# Motor_Schematic.net
KiCad netlist of a schematic drawn in Altium Designer
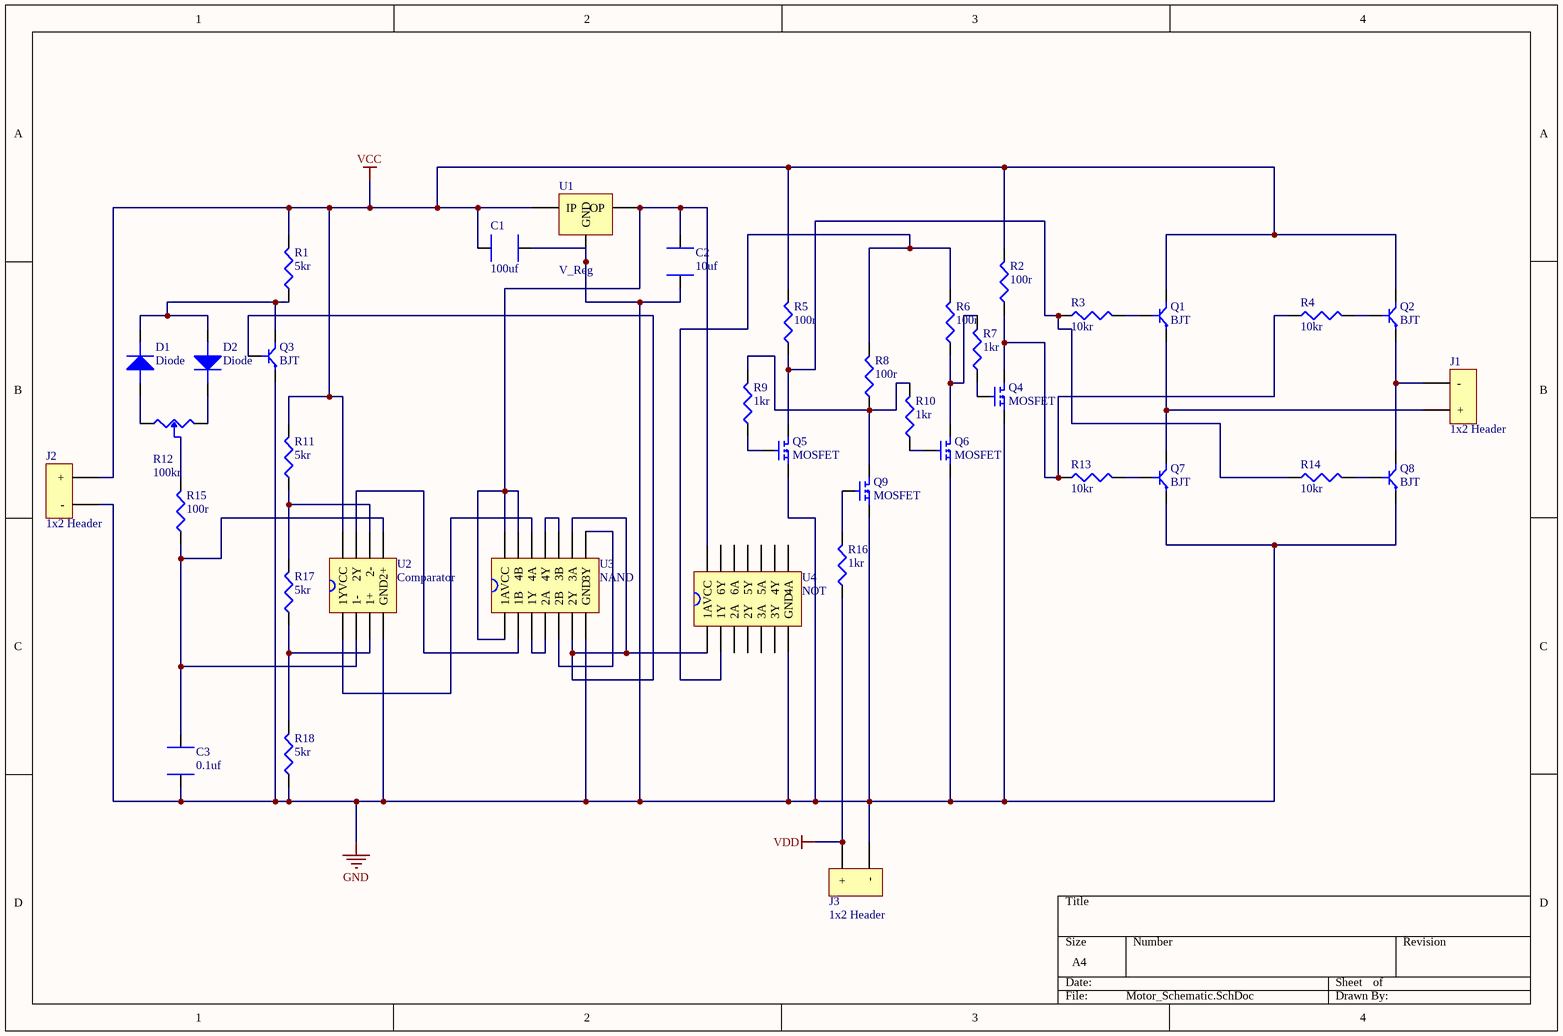
[diagram p0: Motor_Schematic.SchDoc]

(export (version "E")
  (design (tool "Eeschema 10.0.6"))
  (components
    (comp (ref "C1")
      (value "100uf")
      (footprint "100UF")
      (description "CAP CER 100UF 10V Y5V RADIAL")
      (fields (field (name "MANUFACTURER") "TDK") (field (name "MANUFACTURER PART NUMBER") "FK22Y5V1A107Z"))
      (libsource (lib "Sch_Lib") (part "FK22Y5V1A107Z"))
    )
    (comp (ref "C2")
      (value "10uf")
      (footprint "10UF")
      (description "Cap Ceramic 10uF 25V X7R 20% Radial 5mm 125°C Bulk")
      (fields
        (field (name "MANUFACTURER") "TDK")
        (field (name "MANUFACTURER PART NUMBER") "FK20X7R1E106MR000")
      )
      (libsource (lib "Sch_Lib") (part "FK20X7R1E106MR000"))
    )
    (comp (ref "C3")
      (value "0.1uf")
      (footprint "0.1UF")
      (description "Cap Ceramic 0.1uF 50V X7R 10% Radial 5.08mm (0.01%FR) 125°C Bulk")
      (fields
        (field (name "MANUFACTURER") "KEMET")
        (field (name "MANUFACTURER PART NUMBER") "M39014/01-1553")
      )
      (libsource (lib "Sch_Lib") (part "M39014/01-1553"))
    )
    (comp (ref "D1")
      (value "Diode")
      (footprint "Diode")
      (description "DIODE GEN PURP 50V 1A DO41")
      (fields (field (name "MANUFACTURER") "Diodes") (field (name "MANUFACTURER PART NUMBER") "1N4001G-T"))
      (libsource (lib "Sch_Lib") (part "1N4001G-T"))
    )
    (comp (ref "D2")
      (value "Diode")
      (footprint "Diode")
      (description "DIODE GEN PURP 50V 1A DO41")
      (fields (field (name "MANUFACTURER") "Diodes") (field (name "MANUFACTURER PART NUMBER") "1N4001G-T"))
      (libsource (lib "Sch_Lib") (part "1N4001G-T"))
    )
    (comp (ref "J1")
      (value "1x2 Header")
      (footprint "HDR1X2")
      (description "Conn Wire to Board HDR 2 POS 2.54mm Solder ST Thru-Hole Bag")
      (fields (field (name "MANUFACTURER") "Molex") (field (name "MANUFACTURER PART NUMBER") "22-29-2021"))
      (libsource (lib "") (part "22-29-2021_2"))
    )
    (comp (ref "J2")
      (value "1x2 Header")
      (footprint "HDR1X2")
      (description "Conn Wire to Board HDR 2 POS 2.54mm Solder ST Thru-Hole Bag")
      (fields (field (name "MANUFACTURER") "Molex") (field (name "MANUFACTURER PART NUMBER") "22-29-2021"))
      (libsource (lib "Sch_Lib") (part "22-29-2021"))
    )
    (comp (ref "J3")
      (value "1x2 Header")
      (footprint "HDR1X2")
      (description "Conn Wire to Board HDR 2 POS 2.54mm Solder ST Thru-Hole Bag")
      (fields (field (name "MANUFACTURER") "Molex") (field (name "MANUFACTURER PART NUMBER") "22-29-2021"))
      (libsource (lib "") (part "22-29-2021_1"))
    )
    (comp (ref "Q1")
      (value "BJT")
      (footprint "BJT")
      (description "TRANS NPN 40V 0.8A TO-18")
      (fields
        (field (name "MANUFACTURER") "Central Semiconductor")
        (field (name "MANUFACTURER PART NUMBER") "2N2222A")
      )
      (libsource (lib "Sch_Lib") (part "2N2222A"))
    )
    (comp (ref "Q2")
      (value "BJT")
      (footprint "BJT")
      (description "TRANS NPN 40V 0.8A TO-18")
      (fields
        (field (name "MANUFACTURER") "Central Semiconductor")
        (field (name "MANUFACTURER PART NUMBER") "2N2222A")
      )
      (libsource (lib "Sch_Lib") (part "2N2222A"))
    )
    (comp (ref "Q3")
      (value "BJT")
      (footprint "BJT")
      (description "TRANS NPN 40V 0.8A TO-18")
      (fields
        (field (name "MANUFACTURER") "Central Semiconductor")
        (field (name "MANUFACTURER PART NUMBER") "2N2222A")
      )
      (libsource (lib "Sch_Lib") (part "2N2222A"))
    )
    (comp (ref "Q4")
      (value "MOSFET")
      (footprint "MOSFET")
      (description "Trans MOSFET N-CH 60V 0.2A 3-Pin TO-92 Ammo")
      (fields
        (field (name "MANUFACTURER") "ON Semiconductor / Fairchild")
        (field (name "MANUFACTURER PART NUMBER") "2N7000TA")
      )
      (libsource (lib "Sch_Lib") (part "2N7000TA"))
    )
    (comp (ref "Q5")
      (value "MOSFET")
      (footprint "MOSFET")
      (description "Trans MOSFET N-CH 60V 0.2A 3-Pin TO-92 Ammo")
      (fields
        (field (name "MANUFACTURER") "ON Semiconductor / Fairchild")
        (field (name "MANUFACTURER PART NUMBER") "2N7000TA")
      )
      (libsource (lib "Sch_Lib") (part "2N7000TA"))
    )
    (comp (ref "Q6")
      (value "MOSFET")
      (footprint "MOSFET")
      (description "Trans MOSFET N-CH 60V 0.2A 3-Pin TO-92 Ammo")
      (fields
        (field (name "MANUFACTURER") "ON Semiconductor / Fairchild")
        (field (name "MANUFACTURER PART NUMBER") "2N7000TA")
      )
      (libsource (lib "Sch_Lib") (part "2N7000TA"))
    )
    (comp (ref "Q7")
      (value "BJT")
      (footprint "BJT")
      (description "TRANS NPN 40V 0.8A TO-18")
      (fields
        (field (name "MANUFACTURER") "Central Semiconductor")
        (field (name "MANUFACTURER PART NUMBER") "2N2222A")
      )
      (libsource (lib "Sch_Lib") (part "2N2222A"))
    )
    (comp (ref "Q8")
      (value "BJT")
      (footprint "BJT")
      (description "TRANS NPN 40V 0.8A TO-18")
      (fields
        (field (name "MANUFACTURER") "Central Semiconductor")
        (field (name "MANUFACTURER PART NUMBER") "2N2222A")
      )
      (libsource (lib "Sch_Lib") (part "2N2222A"))
    )
    (comp (ref "Q9")
      (value "MOSFET")
      (footprint "MOSFET")
      (description "Trans MOSFET N-CH 60V 0.2A 3-Pin TO-92 Ammo")
      (fields
        (field (name "MANUFACTURER") "ON Semiconductor / Fairchild")
        (field (name "MANUFACTURER PART NUMBER") "2N7000TA")
      )
      (libsource (lib "Sch_Lib") (part "2N7000TA"))
    )
    (comp (ref "R1")
      (value "5kr")
      (footprint "5KR")
      (description "Metal Film Resistors - Through Hole 1/8watt 5Kohms 1% 100ppm Non Std")
      (fields
        (field (name "MANUFACTURER") "Vishay Dale")
        (field (name "MANUFACTURER PART NUMBER") "RN55D5001FB14")
      )
      (libsource (lib "Sch_Lib") (part "RN55D5001FB14"))
    )
    (comp (ref "R2")
      (value "100r")
      (footprint "100R")
      (description "RESISTOR METAL FILM 1W 100 OHM")
      (fields
        (field (name "MANUFACTURER") "Vishay Dale")
        (field (name "MANUFACTURER PART NUMBER") "CPF1100R00JKEE6")
      )
      (libsource (lib "Sch_Lib") (part "CPF1100R00JKEE6"))
    )
    (comp (ref "R3")
      (value "10kr")
      (footprint "10kr")
      (description "RESISTOR METAL FILM 1W 10.0K OHM")
      (fields
        (field (name "MANUFACTURER") "Vishay Dale")
        (field (name "MANUFACTURER PART NUMBER") "CPF110K000FKEE6")
      )
      (libsource (lib "Sch_Lib") (part "CPF110K000FKEE6"))
    )
    (comp (ref "R4")
      (value "10kr")
      (footprint "10kr")
      (description "RESISTOR METAL FILM 1W 10.0K OHM")
      (fields
        (field (name "MANUFACTURER") "Vishay Dale")
        (field (name "MANUFACTURER PART NUMBER") "CPF110K000FKEE6")
      )
      (libsource (lib "Sch_Lib") (part "CPF110K000FKEE6"))
    )
    (comp (ref "R5")
      (value "100r")
      (footprint "100R")
      (description "RESISTOR METAL FILM 1W 100 OHM")
      (fields
        (field (name "MANUFACTURER") "Vishay Dale")
        (field (name "MANUFACTURER PART NUMBER") "CPF1100R00JKEE6")
      )
      (libsource (lib "Sch_Lib") (part "CPF1100R00JKEE6"))
    )
    (comp (ref "R6")
      (value "100r")
      (footprint "100R")
      (description "RESISTOR METAL FILM 1W 100 OHM")
      (fields
        (field (name "MANUFACTURER") "Vishay Dale")
        (field (name "MANUFACTURER PART NUMBER") "CPF1100R00JKEE6")
      )
      (libsource (lib "Sch_Lib") (part "CPF1100R00JKEE6"))
    )
    (comp (ref "R7")
      (value "1kr")
      (footprint "1KR")
      (description "RESISTOR 1.0K OHM 1/4W .01% WW")
      (fields
        (field (name "MANUFACTURER") "Vishay Dale")
        (field (name "MANUFACTURER PART NUMBER") "MR1061K0000TAE66")
      )
      (libsource (lib "Sch_Lib") (part "MR1061K0000TAE66"))
    )
    (comp (ref "R8")
      (value "100r")
      (footprint "100R")
      (description "RESISTOR METAL FILM 1W 100 OHM")
      (fields
        (field (name "MANUFACTURER") "Vishay Dale")
        (field (name "MANUFACTURER PART NUMBER") "CPF1100R00JKEE6")
      )
      (libsource (lib "Sch_Lib") (part "CPF1100R00JKEE6"))
    )
    (comp (ref "R9")
      (value "1kr")
      (footprint "1KR")
      (description "RESISTOR 1.0K OHM 1/4W .01% WW")
      (fields
        (field (name "MANUFACTURER") "Vishay Dale")
        (field (name "MANUFACTURER PART NUMBER") "MR1061K0000TAE66")
      )
      (libsource (lib "Sch_Lib") (part "MR1061K0000TAE66"))
    )
    (comp (ref "R10")
      (value "1kr")
      (footprint "1KR")
      (description "RESISTOR 1.0K OHM 1/4W .01% WW")
      (fields
        (field (name "MANUFACTURER") "Vishay Dale")
        (field (name "MANUFACTURER PART NUMBER") "MR1061K0000TAE66")
      )
      (libsource (lib "Sch_Lib") (part "MR1061K0000TAE66"))
    )
    (comp (ref "R11")
      (value "5kr")
      (footprint "5KR")
      (description "Metal Film Resistors - Through Hole 1/8watt 5Kohms 1% 100ppm Non Std")
      (fields
        (field (name "MANUFACTURER") "Vishay Dale")
        (field (name "MANUFACTURER PART NUMBER") "RN55D5001FB14")
      )
      (libsource (lib "Sch_Lib") (part "RN55D5001FB14"))
    )
    (comp (ref "R12")
      (value "100kr")
      (footprint "POT")
      (description "TRIMMER 100K OHM 0.75W PC PIN")
      (fields (field (name "MANUFACTURER") "TT BI") (field (name "MANUFACTURER PART NUMBER") "89PR100KLF"))
      (libsource (lib "Sch_Lib") (part "89PR100KLF"))
    )
    (comp (ref "R13")
      (value "10kr")
      (footprint "10kr")
      (description "RESISTOR METAL FILM 1W 10.0K OHM")
      (fields
        (field (name "MANUFACTURER") "Vishay Dale")
        (field (name "MANUFACTURER PART NUMBER") "CPF110K000FKEE6")
      )
      (libsource (lib "Sch_Lib") (part "CPF110K000FKEE6"))
    )
    (comp (ref "R14")
      (value "10kr")
      (footprint "10kr")
      (description "RESISTOR METAL FILM 1W 10.0K OHM")
      (fields
        (field (name "MANUFACTURER") "Vishay Dale")
        (field (name "MANUFACTURER PART NUMBER") "CPF110K000FKEE6")
      )
      (libsource (lib "Sch_Lib") (part "CPF110K000FKEE6"))
    )
    (comp (ref "R15")
      (value "100r")
      (footprint "100R")
      (description "RESISTOR METAL FILM 1W 100 OHM")
      (fields
        (field (name "MANUFACTURER") "Vishay Dale")
        (field (name "MANUFACTURER PART NUMBER") "CPF1100R00JKEE6")
      )
      (libsource (lib "Sch_Lib") (part "CPF1100R00JKEE6"))
    )
    (comp (ref "R16")
      (value "1kr")
      (footprint "1KR")
      (description "RESISTOR 1.0K OHM 1/4W .01% WW")
      (fields
        (field (name "MANUFACTURER") "Vishay Dale")
        (field (name "MANUFACTURER PART NUMBER") "MR1061K0000TAE66")
      )
      (libsource (lib "Sch_Lib") (part "MR1061K0000TAE66"))
    )
    (comp (ref "R17")
      (value "5kr")
      (footprint "5KR")
      (description "Metal Film Resistors - Through Hole 1/8watt 5Kohms 1% 100ppm Non Std")
      (fields
        (field (name "MANUFACTURER") "Vishay Dale")
        (field (name "MANUFACTURER PART NUMBER") "RN55D5001FB14")
      )
      (libsource (lib "Sch_Lib") (part "RN55D5001FB14"))
    )
    (comp (ref "R18")
      (value "5kr")
      (footprint "5KR")
      (description "Metal Film Resistors - Through Hole 1/8watt 5Kohms 1% 100ppm Non Std")
      (fields
        (field (name "MANUFACTURER") "Vishay Dale")
        (field (name "MANUFACTURER PART NUMBER") "RN55D5001FB14")
      )
      (libsource (lib "Sch_Lib") (part "RN55D5001FB14"))
    )
    (comp (ref "U1")
      (value "V_Reg")
      (footprint "V_REG")
      (description "IC REG LINEAR 5V 1A TO220-3")
      (fields
        (field (name "MANUFACTURER") "TI National Semiconductor")
        (field (name "MANUFACTURER PART NUMBER") "LM340T-5.0")
      )
      (libsource (lib "Sch_Lib") (part "LM340T-5.0"))
    )
    (comp (ref "U2")
      (value "Comparator")
      (footprint "COMP")
      (description "Comparator Dual ±18V/36V 8-Pin Micro T/R")
      (fields
        (field (name "MANUFACTURER") "ON Semiconductor")
        (field (name "MANUFACTURER PART NUMBER") "LM2903DMR2G")
      )
      (libsource (lib "Sch_Lib") (part "LM2903DMR2G"))
    )
    (comp (ref "U3")
      (value "NAND")
      (footprint "NAND")
      (description "NAND Gate 4-Element 2-IN Bipolar 14-Pin PDIP Tube")
      (fields
        (field (name "MANUFACTURER") "Texas Instruments")
        (field (name "MANUFACTURER PART NUMBER") "SN74AS1000AN")
      )
      (libsource (lib "Sch_Lib") (part "SN74AS1000AN"))
    )
    (comp (ref "U4")
      (value "NOT")
      (footprint "NOT")
      (description "Inverter Schmitt Trigger 6-Element CMOS 14-Pin SOP T/R")
      (fields
        (field (name "MANUFACTURER") "Toshiba")
        (field (name "MANUFACTURER PART NUMBER") "TC74AC14F(EL,F)")
      )
      (libsource (lib "Sch_Lib") (part "TC74AC14F(EL,F)"))
    )
  )
  (nets
    (net (code "1") (name "GND") (class "Default")
      (node (ref "C1") (pin "2") (pinfunction "2_2") (pintype "passive"))
      (node (ref "C2") (pin "1") (pinfunction "1_1") (pintype "passive"))
      (node (ref "C3") (pin "1") (pinfunction "1_1") (pintype "passive"))
      (node (ref "J2") (pin "2") (pinfunction "-_2") (pintype "passive"))
      (node (ref "J3") (pin "2") (pinfunction "-_2") (pintype "passive"))
      (node (ref "Q3") (pin "3") (pinfunction "3_3") (pintype "passive"))
      (node (ref "Q4") (pin "3") (pinfunction "3_3") (pintype "passive"))
      (node (ref "Q5") (pin "3") (pinfunction "3_3") (pintype "passive"))
      (node (ref "Q6") (pin "3") (pinfunction "3_3") (pintype "passive"))
      (node (ref "Q7") (pin "3") (pinfunction "3_3") (pintype "passive"))
      (node (ref "Q8") (pin "3") (pinfunction "3_3") (pintype "passive"))
      (node (ref "Q9") (pin "3") (pinfunction "3_3") (pintype "passive"))
      (node (ref "R18") (pin "1") (pinfunction "1_1") (pintype "passive"))
      (node (ref "U1") (pin "2") (pinfunction "GND_2") (pintype "passive"))
      (node (ref "U2") (pin "4") (pinfunction "GND_4") (pintype "passive"))
      (node (ref "U3") (pin "7") (pinfunction "GND_7") (pintype "passive"))
      (node (ref "U4") (pin "7") (pinfunction "GND_7") (pintype "passive"))
    )
    (net (code "2") (name "Net-(D1-Pad1)") (class "Default")
      (node (ref "D1") (pin "1") (pinfunction "1_1") (pintype "passive"))
      (node (ref "D2") (pin "2") (pinfunction "2_2") (pintype "passive"))
      (node (ref "Q3") (pin "1") (pinfunction "1_1") (pintype "passive"))
      (node (ref "R1") (pin "1") (pinfunction "1_1") (pintype "passive"))
    )
    (net (code "3") (name "Net-(D1-Pad2)") (class "Default")
      (node (ref "D1") (pin "2") (pinfunction "2_2") (pintype "passive"))
      (node (ref "R12") (pin "3") (pinfunction "3_3") (pintype "passive"))
    )
    (net (code "4") (name "Net-(D2-Pad1)") (class "Default")
      (node (ref "D2") (pin "1") (pinfunction "1_1") (pintype "passive"))
      (node (ref "R12") (pin "1") (pinfunction "1_1") (pintype "passive"))
    )
    (net (code "5") (name "Net-(J1-+)") (class "Default")
      (node (ref "J1") (pin "1") (pinfunction "+_1") (pintype "passive"))
      (node (ref "Q1") (pin "3") (pinfunction "3_3") (pintype "passive"))
      (node (ref "Q7") (pin "1") (pinfunction "1_1") (pintype "passive"))
    )
    (net (code "6") (name "Net-(J1--)") (class "Default")
      (node (ref "J1") (pin "2") (pinfunction "-_2") (pintype "passive"))
      (node (ref "Q2") (pin "3") (pinfunction "3_3") (pintype "passive"))
      (node (ref "Q8") (pin "1") (pinfunction "1_1") (pintype "passive"))
    )
    (net (code "7") (name "Net-(Q1-Pad2)") (class "Default")
      (node (ref "Q1") (pin "2") (pinfunction "2_2") (pintype "passive"))
      (node (ref "R3") (pin "2") (pinfunction "2_2") (pintype "passive"))
    )
    (net (code "8") (name "Net-(Q2-Pad2)") (class "Default")
      (node (ref "Q2") (pin "2") (pinfunction "2_2") (pintype "passive"))
      (node (ref "R4") (pin "2") (pinfunction "2_2") (pintype "passive"))
    )
    (net (code "9") (name "Net-(Q4-Pad1)") (class "Default")
      (node (ref "Q4") (pin "1") (pinfunction "1_1") (pintype "passive"))
      (node (ref "R13") (pin "1") (pinfunction "1_1") (pintype "passive"))
      (node (ref "R2") (pin "1") (pinfunction "1_1") (pintype "passive"))
      (node (ref "R4") (pin "1") (pinfunction "1_1") (pintype "passive"))
    )
    (net (code "10") (name "Net-(Q4-Pad2)") (class "Default")
      (node (ref "Q4") (pin "2") (pinfunction "2_2") (pintype "passive"))
      (node (ref "R7") (pin "1") (pinfunction "1_1") (pintype "passive"))
    )
    (net (code "11") (name "Net-(Q5-Pad1)") (class "Default")
      (node (ref "Q5") (pin "1") (pinfunction "1_1") (pintype "passive"))
      (node (ref "R14") (pin "1") (pinfunction "1_1") (pintype "passive"))
      (node (ref "R3") (pin "1") (pinfunction "1_1") (pintype "passive"))
      (node (ref "R5") (pin "1") (pinfunction "1_1") (pintype "passive"))
    )
    (net (code "12") (name "Net-(Q5-Pad2)") (class "Default")
      (node (ref "Q5") (pin "2") (pinfunction "2_2") (pintype "passive"))
      (node (ref "R9") (pin "1") (pinfunction "1_1") (pintype "passive"))
    )
    (net (code "13") (name "Net-(Q6-Pad1)") (class "Default")
      (node (ref "Q6") (pin "1") (pinfunction "1_1") (pintype "passive"))
      (node (ref "R6") (pin "1") (pinfunction "1_1") (pintype "passive"))
      (node (ref "R7") (pin "2") (pinfunction "2_2") (pintype "passive"))
    )
    (net (code "14") (name "Net-(Q6-Pad2)") (class "Default")
      (node (ref "Q6") (pin "2") (pinfunction "2_2") (pintype "passive"))
      (node (ref "R10") (pin "1") (pinfunction "1_1") (pintype "passive"))
    )
    (net (code "15") (name "Net-(Q7-Pad2)") (class "Default")
      (node (ref "Q7") (pin "2") (pinfunction "2_2") (pintype "passive"))
      (node (ref "R13") (pin "2") (pinfunction "2_2") (pintype "passive"))
    )
    (net (code "16") (name "Net-(Q8-Pad2)") (class "Default")
      (node (ref "Q8") (pin "2") (pinfunction "2_2") (pintype "passive"))
      (node (ref "R14") (pin "2") (pinfunction "2_2") (pintype "passive"))
    )
    (net (code "17") (name "Net-(Q9-Pad1)") (class "Default")
      (node (ref "Q9") (pin "1") (pinfunction "1_1") (pintype "passive"))
      (node (ref "R10") (pin "2") (pinfunction "2_2") (pintype "passive"))
      (node (ref "R8") (pin "1") (pinfunction "1_1") (pintype "passive"))
      (node (ref "R9") (pin "2") (pinfunction "2_2") (pintype "passive"))
    )
    (net (code "18") (name "Net-(Q9-Pad2)") (class "Default")
      (node (ref "Q9") (pin "2") (pinfunction "2_2") (pintype "passive"))
      (node (ref "R16") (pin "2") (pinfunction "2_2") (pintype "passive"))
    )
    (net (code "19") (name "Net-(R12-Pad2)") (class "Default")
      (node (ref "R12") (pin "2") (pinfunction "2_2") (pintype "passive"))
      (node (ref "R15") (pin "2") (pinfunction "2_2") (pintype "passive"))
    )
    (net (code "20") (name "Net-(U1-OP)") (class "Default")
      (node (ref "C2") (pin "2") (pinfunction "2_2") (pintype "passive"))
      (node (ref "U1") (pin "3") (pinfunction "OP_3") (pintype "passive"))
      (node (ref "U3") (pin "1") (pinfunction "1A_1") (pintype "passive"))
      (node (ref "U3") (pin "13") (pinfunction "4B_13") (pintype "passive"))
      (node (ref "U3") (pin "14") (pinfunction "VCC_14") (pintype "passive"))
      (node (ref "U4") (pin "14") (pinfunction "VCC_14") (pintype "passive"))
    )
    (net (code "21") (name "Net-(U2-1+)") (class "Default")
      (node (ref "R17") (pin "1") (pinfunction "1_1") (pintype "passive"))
      (node (ref "R18") (pin "2") (pinfunction "2_2") (pintype "passive"))
      (node (ref "U2") (pin "3") (pinfunction "1+_3") (pintype "passive"))
    )
    (net (code "22") (name "Net-(U2-1-)") (class "Default")
      (node (ref "C3") (pin "2") (pinfunction "2_2") (pintype "passive"))
      (node (ref "R15") (pin "1") (pinfunction "1_1") (pintype "passive"))
      (node (ref "U2") (pin "2") (pinfunction "1-_2") (pintype "passive"))
      (node (ref "U2") (pin "5") (pinfunction "2+_5") (pintype "passive"))
    )
    (net (code "23") (name "Net-(U2-1Y)") (class "Default")
      (node (ref "U2") (pin "1") (pinfunction "1Y_1") (pintype "passive"))
      (node (ref "U3") (pin "12") (pinfunction "4A_12") (pintype "passive"))
    )
    (net (code "24") (name "Net-(U2-2-)") (class "Default")
      (node (ref "R11") (pin "1") (pinfunction "1_1") (pintype "passive"))
      (node (ref "R17") (pin "2") (pinfunction "2_2") (pintype "passive"))
      (node (ref "U2") (pin "6") (pinfunction "2-_6") (pintype "passive"))
    )
    (net (code "25") (name "Net-(U2-2Y)") (class "Default")
      (node (ref "U2") (pin "7") (pinfunction "2Y_7") (pintype "passive"))
      (node (ref "U3") (pin "2") (pinfunction "1B_2") (pintype "passive"))
    )
    (net (code "26") (name "Net-(U3-1Y)") (class "Default")
      (node (ref "U3") (pin "3") (pinfunction "1Y_3") (pintype "passive"))
      (node (ref "U3") (pin "4") (pinfunction "2A_4") (pintype "passive"))
    )
    (net (code "27") (name "Net-(U3-2B)") (class "Default")
      (node (ref "U3") (pin "5") (pinfunction "2B_5") (pintype "passive"))
      (node (ref "U3") (pin "8") (pinfunction "3Y_8") (pintype "passive"))
    )
    (net (code "28") (name "Net-(U3-2Y)") (class "Default")
      (node (ref "Q3") (pin "2") (pinfunction "2_2") (pintype "passive"))
      (node (ref "U3") (pin "6") (pinfunction "2Y_6") (pintype "passive"))
      (node (ref "U3") (pin "9") (pinfunction "3A_9") (pintype "passive"))
      (node (ref "U4") (pin "1") (pinfunction "1A_1") (pintype "passive"))
    )
    (net (code "29") (name "Net-(U3-3B)") (class "Default")
      (node (ref "U3") (pin "10") (pinfunction "3B_10") (pintype "passive"))
      (node (ref "U3") (pin "11") (pinfunction "4Y_11") (pintype "passive"))
    )
    (net (code "30") (name "Net-(U4-1Y)") (class "Default")
      (node (ref "R6") (pin "2") (pinfunction "2_2") (pintype "passive"))
      (node (ref "R8") (pin "2") (pinfunction "2_2") (pintype "passive"))
      (node (ref "U4") (pin "2") (pinfunction "1Y_2") (pintype "passive"))
    )
    (net (code "31") (name "VCC") (class "Default")
      (node (ref "C1") (pin "1") (pinfunction "1_1") (pintype "passive"))
      (node (ref "J2") (pin "1") (pinfunction "+_1") (pintype "passive"))
      (node (ref "Q1") (pin "1") (pinfunction "1_1") (pintype "passive"))
      (node (ref "Q2") (pin "1") (pinfunction "1_1") (pintype "passive"))
      (node (ref "R1") (pin "2") (pinfunction "2_2") (pintype "passive"))
      (node (ref "R11") (pin "2") (pinfunction "2_2") (pintype "passive"))
      (node (ref "R2") (pin "2") (pinfunction "2_2") (pintype "passive"))
      (node (ref "R5") (pin "2") (pinfunction "2_2") (pintype "passive"))
      (node (ref "U1") (pin "1") (pinfunction "IP_1") (pintype "passive"))
      (node (ref "U2") (pin "8") (pinfunction "VCC_8") (pintype "passive"))
    )
    (net (code "32") (name "VDD") (class "Default")
      (node (ref "J3") (pin "1") (pinfunction "+_1") (pintype "passive"))
      (node (ref "R16") (pin "1") (pinfunction "1_1") (pintype "passive"))
    )
    (net (code "33") (name "unconnected-(U4-2A-Pad3)") (class "Default")
      (node (ref "U4") (pin "3") (pinfunction "2A_3") (pintype "passive"))
    )
    (net (code "34") (name "unconnected-(U4-2Y-Pad4)") (class "Default")
      (node (ref "U4") (pin "4") (pinfunction "2Y_4") (pintype "passive"))
    )
    (net (code "35") (name "unconnected-(U4-3A-Pad5)") (class "Default")
      (node (ref "U4") (pin "5") (pinfunction "3A_5") (pintype "passive"))
    )
    (net (code "36") (name "unconnected-(U4-3Y-Pad6)") (class "Default")
      (node (ref "U4") (pin "6") (pinfunction "3Y_6") (pintype "passive"))
    )
    (net (code "37") (name "unconnected-(U4-4A-Pad8)") (class "Default")
      (node (ref "U4") (pin "8") (pinfunction "4A_8") (pintype "passive"))
    )
    (net (code "38") (name "unconnected-(U4-4Y-Pad9)") (class "Default")
      (node (ref "U4") (pin "9") (pinfunction "4Y_9") (pintype "passive"))
    )
    (net (code "39") (name "unconnected-(U4-5A-Pad10)") (class "Default")
      (node (ref "U4") (pin "10") (pinfunction "5A_10") (pintype "passive"))
    )
    (net (code "40") (name "unconnected-(U4-5Y-Pad11)") (class "Default")
      (node (ref "U4") (pin "11") (pinfunction "5Y_11") (pintype "passive"))
    )
    (net (code "41") (name "unconnected-(U4-6A-Pad12)") (class "Default")
      (node (ref "U4") (pin "12") (pinfunction "6A_12") (pintype "passive"))
    )
    (net (code "42") (name "unconnected-(U4-6Y-Pad13)") (class "Default")
      (node (ref "U4") (pin "13") (pinfunction "6Y_13") (pintype "passive"))
    )
  )
)
